# femtoBeacon_dongle_r2_0_6_RGB.net
KiCad netlist of a schematic drawn in EAGLE
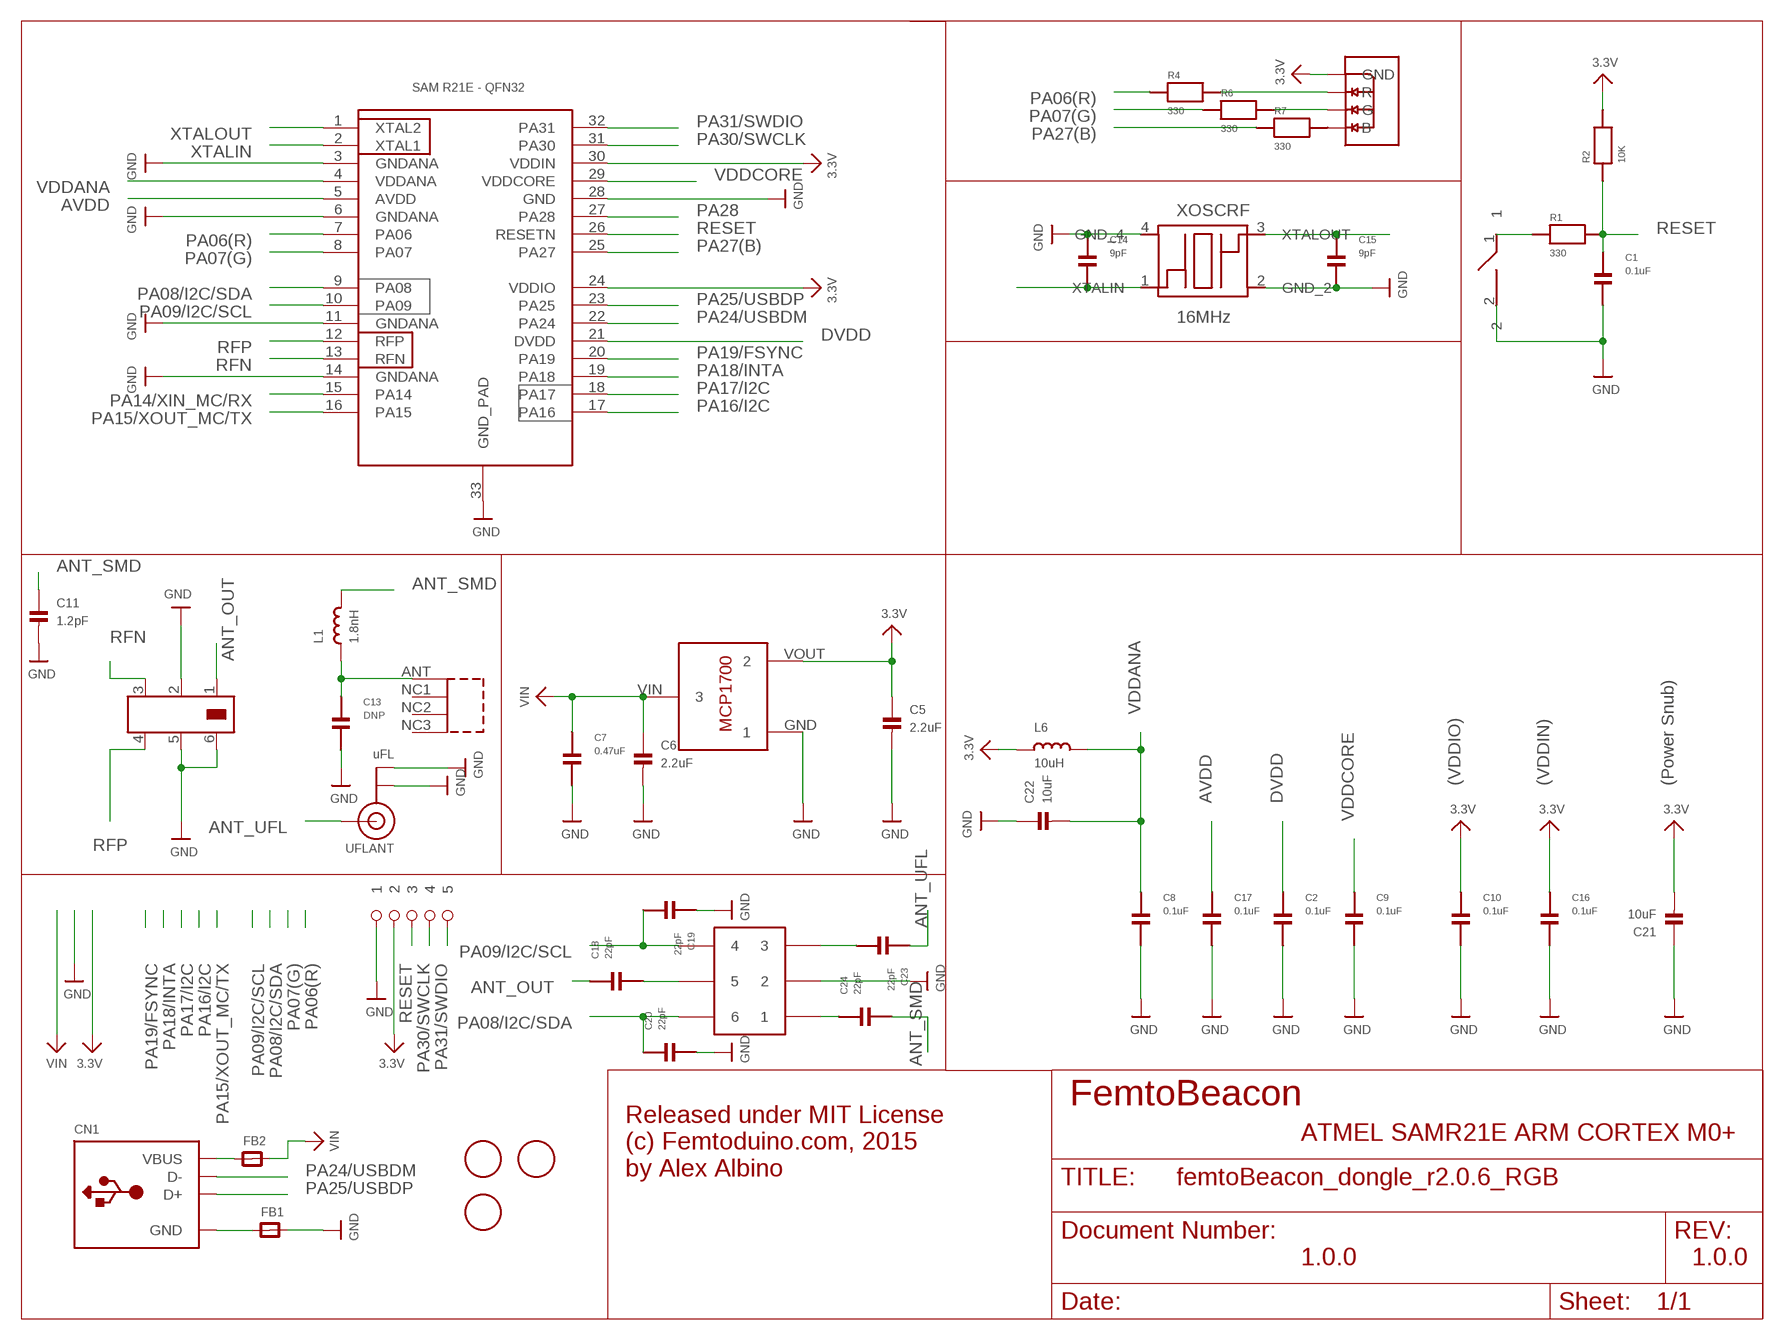
[diagram p0: schematic, sheet 1]

(export (version "E")
  (design (tool "Eeschema 10.0.6"))
  (components
    (comp (ref "ASWITCH")
      (value "AS222-92LF")
      (footprint "eagle-import:AS222-92LF")
      (libsource (lib "eagle-import") (part "AS222-92LF"))
    )
    (comp (ref "BTN")
      (value "DNP")
      (footprint "eagle-import:SPST_SMD")
      (libsource (lib "eagle-import") (part "SPST_SMD"))
    )
    (comp (ref "C1")
      (value "0.1uF")
      (footprint "eagle-import:PART")
      (libsource (lib "eagle-import") (part "CAPACITOR_0201"))
    )
    (comp (ref "C2")
      (value "0.1uF")
      (footprint "eagle-import:PART")
      (libsource (lib "eagle-import") (part "CAPACITOR_0201"))
    )
    (comp (ref "C5")
      (value "2.2uF")
      (footprint "eagle-import:_0402MP")
      (libsource (lib "eagle-import") (part "CAP_CERAMIC_0402MP"))
    )
    (comp (ref "C6")
      (value "2.2uF")
      (footprint "eagle-import:_0402MP")
      (libsource (lib "eagle-import") (part "CAP_CERAMIC_0402MP"))
    )
    (comp (ref "C7")
      (value "0.47uF")
      (footprint "eagle-import:PART")
      (libsource (lib "eagle-import") (part "CAPACITOR_0201"))
    )
    (comp (ref "C8")
      (value "0.1uF")
      (footprint "eagle-import:PART")
      (libsource (lib "eagle-import") (part "CAPACITOR_0201"))
    )
    (comp (ref "C9")
      (value "0.1uF")
      (footprint "eagle-import:PART")
      (libsource (lib "eagle-import") (part "CAPACITOR_0201"))
    )
    (comp (ref "C10")
      (value "0.1uF")
      (footprint "eagle-import:PART")
      (libsource (lib "eagle-import") (part "CAPACITOR_0201"))
    )
    (comp (ref "C11")
      (value "1.2pF")
      (footprint "eagle-import:_0402MP")
      (libsource (lib "eagle-import") (part "CAP_CERAMIC_0402MP"))
    )
    (comp (ref "C13")
      (value "DNP")
      (footprint "eagle-import:PART")
      (libsource (lib "eagle-import") (part "CAPACITOR_0201"))
    )
    (comp (ref "C14")
      (value "9pF")
      (footprint "eagle-import:PART")
      (libsource (lib "eagle-import") (part "CAPACITOR_0201"))
    )
    (comp (ref "C15")
      (value "9pF")
      (footprint "eagle-import:PART")
      (libsource (lib "eagle-import") (part "CAPACITOR_0201"))
    )
    (comp (ref "C16")
      (value "0.1uF")
      (footprint "eagle-import:PART")
      (libsource (lib "eagle-import") (part "CAPACITOR_0201"))
    )
    (comp (ref "C17")
      (value "0.1uF")
      (footprint "eagle-import:PART")
      (libsource (lib "eagle-import") (part "CAPACITOR_0201"))
    )
    (comp (ref "C18")
      (value "22pF")
      (footprint "eagle-import:PART")
      (libsource (lib "eagle-import") (part "CAPACITOR_0201"))
    )
    (comp (ref "C19")
      (value "22pF")
      (footprint "eagle-import:PART")
      (libsource (lib "eagle-import") (part "CAPACITOR_0201"))
    )
    (comp (ref "C20")
      (value "22pF")
      (footprint "eagle-import:PART")
      (libsource (lib "eagle-import") (part "CAPACITOR_0201"))
    )
    (comp (ref "C21")
      (value "10uF")
      (footprint "eagle-import:_0402MP")
      (libsource (lib "eagle-import") (part "CAP_CERAMIC_0402MP"))
    )
    (comp (ref "C22")
      (value "10uF")
      (footprint "eagle-import:_0402MP")
      (libsource (lib "eagle-import") (part "CAP_CERAMIC_0402MP"))
    )
    (comp (ref "C23")
      (value "22pF")
      (footprint "eagle-import:PART")
      (libsource (lib "eagle-import") (part "CAPACITOR_0201"))
    )
    (comp (ref "C24")
      (value "22pF")
      (footprint "eagle-import:PART")
      (libsource (lib "eagle-import") (part "CAPACITOR_0201"))
    )
    (comp (ref "CN1")
      (value "USB_TYPEA")
      (footprint "eagle-import:USB_A-SMT")
      (libsource (lib "eagle-import") (part "USB_TYPEA"))
    )
    (comp (ref "FB1")
      (value "FERRITE_0603MP")
      (footprint "eagle-import:_0603MP")
      (libsource (lib "eagle-import") (part "FERRITE_0603MP"))
    )
    (comp (ref "FB2")
      (value "FERRITE_0603MP")
      (footprint "eagle-import:_0603MP")
      (libsource (lib "eagle-import") (part "FERRITE_0603MP"))
    )
    (comp (ref "FID1")
      (value "FIDUCIAL")
      (footprint "eagle-import:FIDUCIAL_1MM")
      (libsource (lib "eagle-import") (part "FIDUCIAL"))
    )
    (comp (ref "FID2")
      (value "FIDUCIAL")
      (footprint "eagle-import:FIDUCIAL_1MM")
      (libsource (lib "eagle-import") (part "FIDUCIAL"))
    )
    (comp (ref "FID3")
      (value "FIDUCIAL")
      (footprint "eagle-import:FIDUCIAL_1MM")
      (libsource (lib "eagle-import") (part "FIDUCIAL"))
    )
    (comp (ref "L1")
      (value "1.8nH")
      (footprint "eagle-import:_0603MP")
      (libsource (lib "eagle-import") (part "INDUCTOR_0603MP"))
    )
    (comp (ref "L6")
      (value "10uH")
      (footprint "eagle-import:_0603MP")
      (libsource (lib "eagle-import") (part "INDUCTOR_0603MP"))
    )
    (comp (ref "LDO_VREG")
      (value "MCP1700T-3302E/TT")
      (footprint "eagle-import:MCP1700T-3302E_TT")
      (libsource (lib "eagle-import") (part "MCP1700T-3302E/TT"))
    )
    (comp (ref "R1")
      (value "330")
      (footprint "eagle-import:PART")
      (libsource (lib "eagle-import") (part "RESISTOR_0201"))
    )
    (comp (ref "R2")
      (value "10K")
      (footprint "eagle-import:PART")
      (libsource (lib "eagle-import") (part "RESISTOR_0201"))
    )
    (comp (ref "R4")
      (value "330")
      (footprint "eagle-import:PART")
      (libsource (lib "eagle-import") (part "RESISTOR_0201"))
    )
    (comp (ref "R6")
      (value "330")
      (footprint "eagle-import:PART")
      (libsource (lib "eagle-import") (part "RESISTOR_0201"))
    )
    (comp (ref "R7")
      (value "330")
      (footprint "eagle-import:PART")
      (libsource (lib "eagle-import") (part "RESISTOR_0201"))
    )
    (comp (ref "RGBLED")
      (value "LRTB_R48G")
      (footprint "eagle-import:LRTB_R48G")
      (libsource (lib "eagle-import") (part "LRTB_R48G"))
    )
    (comp (ref "U$1")
      (value "1X5_ROUND")
      (footprint "eagle-import:1X5_ROUND")
      (libsource (lib "eagle-import") (part "1X5_ROUND"))
    )
    (comp (ref "U$6")
      (value "0479480001")
      (footprint "eagle-import:0479480001")
      (libsource (lib "eagle-import") (part "0479480001"))
    )
    (comp (ref "U$12")
      (value "JOHANSON_2450BM15A0015E")
      (footprint "eagle-import:0805_BALUN")
      (libsource (lib "eagle-import") (part "JOHANSON_2450BM15A0015E"))
    )
    (comp (ref "U$76")
      (value "ATSAMR21E18A-MUT")
      (footprint "eagle-import:QFN32")
      (libsource (lib "eagle-import") (part "ATSAMR21E18A-MUT"))
    )
    (comp (ref "UFLANT")
      (value "uFL")
      (footprint "eagle-import:U.FL")
      (libsource (lib "eagle-import") (part "ANTENNA_U.FL"))
    )
    (comp (ref "XOSCRF")
      (value "16MHz")
      (footprint "eagle-import:TSX-3225")
      (libsource (lib "eagle-import") (part "TSX-3225"))
    )
  )
  (nets
    (net (code "1") (name "/ANT_OUT") (class "Default")
      (node (ref "C18") (pin "1") (pinfunction "P$1_1") (pintype "bidirectional"))
      (node (ref "U$12") (pin "1") (pinfunction "1_1") (pintype "bidirectional"))
    )
    (net (code "2") (name "/ANT_SMD") (class "Default")
      (node (ref "C11") (pin "1") (pinfunction "P$1_1") (pintype "passive"))
      (node (ref "C24") (pin "2") (pinfunction "P$2_2") (pintype "bidirectional"))
      (node (ref "L1") (pin "2") (pinfunction "2_2") (pintype "passive"))
    )
    (net (code "3") (name "/ANT_UFL") (class "Default")
      (node (ref "C23") (pin "1") (pinfunction "P$1_1") (pintype "bidirectional"))
      (node (ref "UFLANT") (pin "3") (pinfunction "SIGNAL_3") (pintype "passive"))
    )
    (net (code "4") (name "/AVDD") (class "Default")
      (node (ref "C17") (pin "1") (pinfunction "P$1_1") (pintype "bidirectional"))
      (node (ref "U$76") (pin "5") (pinfunction "AVDD_5") (pintype "bidirectional"))
    )
    (net (code "5") (name "/DVDD") (class "Default")
      (node (ref "C2") (pin "1") (pinfunction "P$1_1") (pintype "bidirectional"))
      (node (ref "U$76") (pin "21") (pinfunction "DVDD_21") (pintype "bidirectional"))
    )
    (net (code "6") (name "/PA06(R)") (class "Default")
      (node (ref "R4") (pin "1") (pinfunction "1_1") (pintype "bidirectional"))
      (node (ref "U$76") (pin "7") (pinfunction "PA06_7") (pintype "bidirectional"))
    )
    (net (code "7") (name "/PA07(G)") (class "Default")
      (node (ref "R6") (pin "1") (pinfunction "1_1") (pintype "bidirectional"))
      (node (ref "U$76") (pin "8") (pinfunction "PA07_8") (pintype "bidirectional"))
    )
    (net (code "8") (name "/PA08{slash}I2C{slash}SDA") (class "Default")
      (node (ref "ASWITCH") (pin "PIN6") (pinfunction "6_PIN6") (pintype "bidirectional"))
      (node (ref "C20") (pin "1") (pinfunction "P$1_1") (pintype "bidirectional"))
      (node (ref "U$76") (pin "9") (pinfunction "PA08_9") (pintype "bidirectional"))
    )
    (net (code "9") (name "/PA09{slash}I2C{slash}SCL") (class "Default")
      (node (ref "ASWITCH") (pin "PIN4") (pinfunction "4_PIN4") (pintype "bidirectional"))
      (node (ref "C19") (pin "2") (pinfunction "P$2_2") (pintype "bidirectional"))
      (node (ref "U$76") (pin "10") (pinfunction "PA09_10") (pintype "bidirectional"))
    )
    (net (code "10") (name "/PA14{slash}XIN_MC{slash}RX") (class "Default")
      (node (ref "U$76") (pin "15") (pinfunction "PA14_15") (pintype "bidirectional"))
    )
    (net (code "11") (name "/PA15{slash}XOUT_MC{slash}TX") (class "Default")
      (node (ref "U$76") (pin "16") (pinfunction "PA15_16") (pintype "bidirectional"))
    )
    (net (code "12") (name "/PA16{slash}I2C") (class "Default")
      (node (ref "U$76") (pin "17") (pinfunction "PA16_17") (pintype "bidirectional"))
    )
    (net (code "13") (name "/PA17{slash}I2C") (class "Default")
      (node (ref "U$76") (pin "18") (pinfunction "PA17_18") (pintype "bidirectional"))
    )
    (net (code "14") (name "/PA18{slash}INTA") (class "Default")
      (node (ref "U$76") (pin "19") (pinfunction "PA18_19") (pintype "bidirectional"))
    )
    (net (code "15") (name "/PA19{slash}FSYNC") (class "Default")
      (node (ref "U$76") (pin "20") (pinfunction "PA19_20") (pintype "bidirectional"))
    )
    (net (code "16") (name "/PA24{slash}USBDM") (class "Default")
      (node (ref "CN1") (pin "D-") (pinfunction "D-_D-") (pintype "bidirectional"))
      (node (ref "U$76") (pin "22") (pinfunction "PA24_22") (pintype "bidirectional"))
    )
    (net (code "17") (name "/PA25{slash}USBDP") (class "Default")
      (node (ref "CN1") (pin "D+") (pinfunction "D+_D+") (pintype "bidirectional"))
      (node (ref "U$76") (pin "23") (pinfunction "PA25_23") (pintype "bidirectional"))
    )
    (net (code "18") (name "/PA27(B)") (class "Default")
      (node (ref "R7") (pin "1") (pinfunction "1_1") (pintype "bidirectional"))
      (node (ref "U$76") (pin "25") (pinfunction "PA27_25") (pintype "bidirectional"))
    )
    (net (code "19") (name "/PA28") (class "Default")
      (node (ref "U$76") (pin "27") (pinfunction "PA28_27") (pintype "bidirectional"))
    )
    (net (code "20") (name "/PA30{slash}SWCLK") (class "Default")
      (node (ref "U$1") (pin "P$4") (pinfunction "4_P$4") (pintype "bidirectional"))
      (node (ref "U$76") (pin "31") (pinfunction "PA30_31") (pintype "bidirectional"))
    )
    (net (code "21") (name "/PA31{slash}SWDIO") (class "Default")
      (node (ref "U$1") (pin "P$5") (pinfunction "5_P$5") (pintype "bidirectional"))
      (node (ref "U$76") (pin "32") (pinfunction "PA31_32") (pintype "bidirectional"))
    )
    (net (code "22") (name "/RESET") (class "Default")
      (node (ref "C1") (pin "1") (pinfunction "P$1_1") (pintype "bidirectional"))
      (node (ref "R1") (pin "2") (pinfunction "2_2") (pintype "bidirectional"))
      (node (ref "R2") (pin "1") (pinfunction "1_1") (pintype "bidirectional"))
      (node (ref "U$1") (pin "P$3") (pinfunction "3_P$3") (pintype "bidirectional"))
      (node (ref "U$76") (pin "26") (pinfunction "RESETN_26") (pintype "bidirectional"))
    )
    (net (code "23") (name "/RFN") (class "Default")
      (node (ref "U$12") (pin "3") (pinfunction "3_3") (pintype "bidirectional"))
      (node (ref "U$76") (pin "13") (pinfunction "RFN_13") (pintype "bidirectional"))
    )
    (net (code "24") (name "/RFP") (class "Default")
      (node (ref "U$12") (pin "4") (pinfunction "4_4") (pintype "bidirectional"))
      (node (ref "U$76") (pin "12") (pinfunction "RFP_12") (pintype "bidirectional"))
    )
    (net (code "25") (name "/VDDANA") (class "Default")
      (node (ref "C22") (pin "2") (pinfunction "P$2_2") (pintype "passive"))
      (node (ref "C8") (pin "1") (pinfunction "P$1_1") (pintype "bidirectional"))
      (node (ref "L6") (pin "2") (pinfunction "2_2") (pintype "passive"))
      (node (ref "U$76") (pin "4") (pinfunction "VDDANA_4") (pintype "bidirectional"))
    )
    (net (code "26") (name "/VDDCORE") (class "Default")
      (node (ref "C9") (pin "1") (pinfunction "P$1_1") (pintype "bidirectional"))
      (node (ref "U$76") (pin "29") (pinfunction "VDDCORE_29") (pintype "bidirectional"))
    )
    (net (code "27") (name "/XTALIN") (class "Default")
      (node (ref "C14") (pin "2") (pinfunction "P$2_2") (pintype "bidirectional"))
      (node (ref "U$76") (pin "2") (pinfunction "XTAL1_2") (pintype "bidirectional"))
      (node (ref "XOSCRF") (pin "1") (pinfunction "XTALIN_1") (pintype "bidirectional"))
    )
    (net (code "28") (name "/XTALOUT") (class "Default")
      (node (ref "C15") (pin "1") (pinfunction "P$1_1") (pintype "bidirectional"))
      (node (ref "U$76") (pin "1") (pinfunction "XTAL2_1") (pintype "bidirectional"))
      (node (ref "XOSCRF") (pin "3") (pinfunction "XTALOUT_3") (pintype "bidirectional"))
    )
    (net (code "29") (name "3.3V") (class "Default")
      (node (ref "C10") (pin "1") (pinfunction "P$1_1") (pintype "bidirectional"))
      (node (ref "C16") (pin "1") (pinfunction "P$1_1") (pintype "bidirectional"))
      (node (ref "C21") (pin "2") (pinfunction "P$2_2") (pintype "passive"))
      (node (ref "C5") (pin "1") (pinfunction "P$1_1") (pintype "passive"))
      (node (ref "L6") (pin "1") (pinfunction "1_1") (pintype "passive"))
      (node (ref "LDO_VREG") (pin "VOUT") (pinfunction "2_VOUT") (pintype "bidirectional"))
      (node (ref "R2") (pin "2") (pinfunction "2_2") (pintype "bidirectional"))
      (node (ref "RGBLED") (pin "1") (pinfunction "GND_1") (pintype "bidirectional"))
      (node (ref "U$1") (pin "P$2") (pinfunction "2_P$2") (pintype "bidirectional"))
      (node (ref "U$76") (pin "24") (pinfunction "VDDIO_24") (pintype "bidirectional"))
      (node (ref "U$76") (pin "30") (pinfunction "VDDIN_30") (pintype "bidirectional"))
    )
    (net (code "30") (name "GND") (class "Default")
      (node (ref "ASWITCH") (pin "PIN2") (pinfunction "2_PIN2") (pintype "bidirectional"))
      (node (ref "BTN") (pin "2") (pinfunction "2_2") (pintype "bidirectional"))
      (node (ref "C1") (pin "2") (pinfunction "P$2_2") (pintype "bidirectional"))
      (node (ref "C10") (pin "2") (pinfunction "P$2_2") (pintype "bidirectional"))
      (node (ref "C11") (pin "2") (pinfunction "P$2_2") (pintype "passive"))
      (node (ref "C13") (pin "2") (pinfunction "P$2_2") (pintype "bidirectional"))
      (node (ref "C14") (pin "1") (pinfunction "P$1_1") (pintype "bidirectional"))
      (node (ref "C15") (pin "2") (pinfunction "P$2_2") (pintype "bidirectional"))
      (node (ref "C16") (pin "2") (pinfunction "P$2_2") (pintype "bidirectional"))
      (node (ref "C17") (pin "2") (pinfunction "P$2_2") (pintype "bidirectional"))
      (node (ref "C19") (pin "1") (pinfunction "P$1_1") (pintype "bidirectional"))
      (node (ref "C2") (pin "2") (pinfunction "P$2_2") (pintype "bidirectional"))
      (node (ref "C20") (pin "2") (pinfunction "P$2_2") (pintype "bidirectional"))
      (node (ref "C21") (pin "1") (pinfunction "P$1_1") (pintype "passive"))
      (node (ref "C22") (pin "1") (pinfunction "P$1_1") (pintype "passive"))
      (node (ref "C5") (pin "2") (pinfunction "P$2_2") (pintype "passive"))
      (node (ref "C6") (pin "2") (pinfunction "P$2_2") (pintype "passive"))
      (node (ref "C7") (pin "2") (pinfunction "P$2_2") (pintype "bidirectional"))
      (node (ref "C8") (pin "2") (pinfunction "P$2_2") (pintype "bidirectional"))
      (node (ref "C9") (pin "2") (pinfunction "P$2_2") (pintype "bidirectional"))
      (node (ref "FB1") (pin "2") (pinfunction "P$2_2") (pintype "passive"))
      (node (ref "LDO_VREG") (pin "GND") (pinfunction "1_GND") (pintype "bidirectional"))
      (node (ref "U$1") (pin "P$1") (pinfunction "1_P$1") (pintype "bidirectional"))
      (node (ref "U$12") (pin "2") (pinfunction "2_2") (pintype "bidirectional"))
      (node (ref "U$12") (pin "5") (pinfunction "5_5") (pintype "bidirectional"))
      (node (ref "U$12") (pin "6") (pinfunction "6_6") (pintype "bidirectional"))
      (node (ref "U$76") (pin "11") (pinfunction "GNDANA_11") (pintype "bidirectional"))
      (node (ref "U$76") (pin "14") (pinfunction "GNDANA_14") (pintype "bidirectional"))
      (node (ref "U$76") (pin "28") (pinfunction "GND_28") (pintype "bidirectional"))
      (node (ref "U$76") (pin "3") (pinfunction "GNDANA_3") (pintype "bidirectional"))
      (node (ref "U$76") (pin "33") (pinfunction "GND_PAD_33") (pintype "bidirectional"))
      (node (ref "U$76") (pin "6") (pinfunction "GNDANA_6") (pintype "bidirectional"))
      (node (ref "UFLANT") (pin "1") (pinfunction "GND_1") (pintype "passive"))
      (node (ref "UFLANT") (pin "2") (pinfunction "GND_2") (pintype "passive"))
      (node (ref "XOSCRF") (pin "2") (pinfunction "GND_2_2") (pintype "bidirectional"))
      (node (ref "XOSCRF") (pin "4") (pinfunction "GND_4_4") (pintype "bidirectional"))
    )
    (net (code "31") (name "Net-(ASWITCH-1)") (class "Default")
      (node (ref "ASWITCH") (pin "PIN1") (pinfunction "1_PIN1") (pintype "bidirectional"))
      (node (ref "C24") (pin "1") (pinfunction "P$1_1") (pintype "bidirectional"))
    )
    (net (code "32") (name "Net-(ASWITCH-3)") (class "Default")
      (node (ref "ASWITCH") (pin "PIN3") (pinfunction "3_PIN3") (pintype "bidirectional"))
      (node (ref "C23") (pin "2") (pinfunction "P$2_2") (pintype "bidirectional"))
    )
    (net (code "33") (name "Net-(ASWITCH-5)") (class "Default")
      (node (ref "ASWITCH") (pin "PIN5") (pinfunction "5_PIN5") (pintype "bidirectional"))
      (node (ref "C18") (pin "2") (pinfunction "P$2_2") (pintype "bidirectional"))
    )
    (net (code "34") (name "Net-(BTN-Pad1)") (class "Default")
      (node (ref "BTN") (pin "1") (pinfunction "1_1") (pintype "bidirectional"))
      (node (ref "R1") (pin "1") (pinfunction "1_1") (pintype "bidirectional"))
    )
    (net (code "35") (name "Net-(C13-P$1)") (class "Default")
      (node (ref "C13") (pin "1") (pinfunction "P$1_1") (pintype "bidirectional"))
      (node (ref "L1") (pin "1") (pinfunction "1_1") (pintype "passive"))
      (node (ref "U$6") (pin "ANT") (pinfunction "1_ANT") (pintype "bidirectional"))
    )
    (net (code "36") (name "Net-(FB1-P$1)") (class "Default")
      (node (ref "CN1") (pin "GND") (pinfunction "GND_GND") (pintype "power_in"))
      (node (ref "FB1") (pin "1") (pinfunction "P$1_1") (pintype "passive"))
    )
    (net (code "37") (name "Net-(FB2-P$1)") (class "Default")
      (node (ref "CN1") (pin "VBUS") (pinfunction "VBUS_VBUS") (pintype "power_in"))
      (node (ref "FB2") (pin "1") (pinfunction "P$1_1") (pintype "passive"))
    )
    (net (code "38") (name "Net-(RGBLED-B)") (class "Default")
      (node (ref "R7") (pin "2") (pinfunction "2_2") (pintype "bidirectional"))
      (node (ref "RGBLED") (pin "4") (pinfunction "B_4") (pintype "bidirectional"))
    )
    (net (code "39") (name "Net-(RGBLED-G)") (class "Default")
      (node (ref "R6") (pin "2") (pinfunction "2_2") (pintype "bidirectional"))
      (node (ref "RGBLED") (pin "3") (pinfunction "G_3") (pintype "bidirectional"))
    )
    (net (code "40") (name "Net-(RGBLED-R)") (class "Default")
      (node (ref "R4") (pin "2") (pinfunction "2_2") (pintype "bidirectional"))
      (node (ref "RGBLED") (pin "2") (pinfunction "R_2") (pintype "bidirectional"))
    )
    (net (code "41") (name "VIN") (class "Default")
      (node (ref "C6") (pin "1") (pinfunction "P$1_1") (pintype "passive"))
      (node (ref "C7") (pin "1") (pinfunction "P$1_1") (pintype "bidirectional"))
      (node (ref "FB2") (pin "2") (pinfunction "P$2_2") (pintype "passive"))
      (node (ref "LDO_VREG") (pin "VIN") (pinfunction "3_VIN") (pintype "bidirectional"))
    )
    (net (code "42") (name "unconnected-(U$6-2-PadNC1)") (class "Default")
      (node (ref "U$6") (pin "NC1") (pinfunction "2_NC1") (pintype "bidirectional"))
    )
    (net (code "43") (name "unconnected-(U$6-3-PadNC2)") (class "Default")
      (node (ref "U$6") (pin "NC2") (pinfunction "3_NC2") (pintype "bidirectional"))
    )
    (net (code "44") (name "unconnected-(U$6-4-PadNC3)") (class "Default")
      (node (ref "U$6") (pin "NC3") (pinfunction "4_NC3") (pintype "bidirectional"))
    )
  )
)
